# atmega328_Arduino.net
KiCad netlist of a schematic drawn in EAGLE
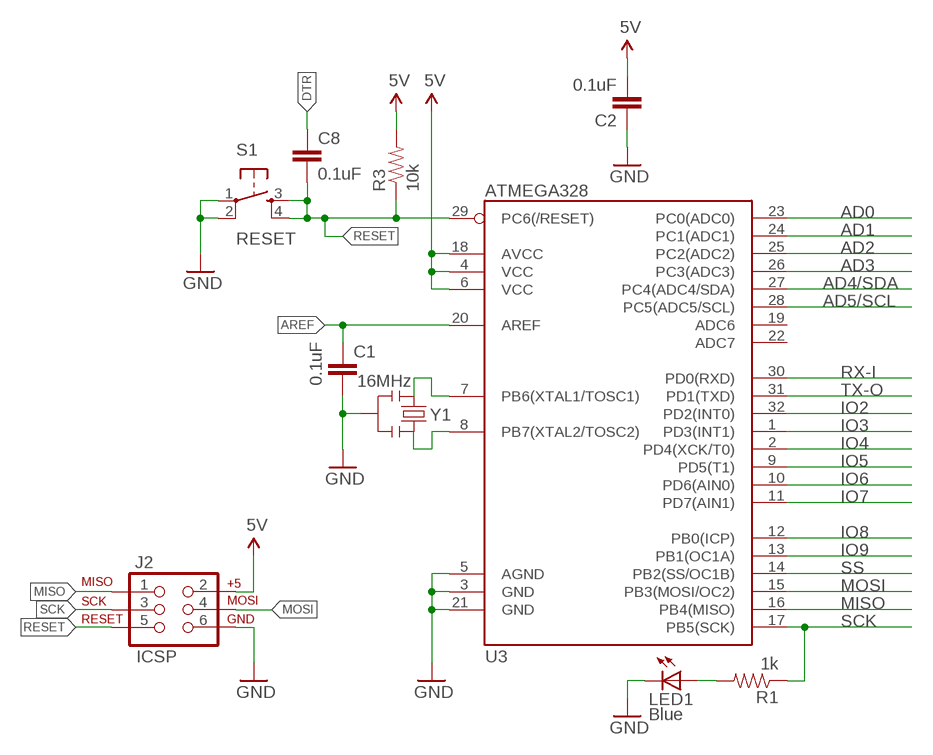
[diagram p0: schematic, sheet 1]

(export (version "E")
  (design (tool "Eeschema 10.0.6"))
  (components
    (comp (ref "C1")
      (value "0.1uF")
      (footprint "eagle-import:0603-CAP")
      (libsource (lib "eagle-import") (part "CAP0603-CAP"))
    )
    (comp (ref "C2")
      (value "0.1uF")
      (footprint "eagle-import:0603-CAP")
      (libsource (lib "eagle-import") (part "CAP0603-CAP"))
    )
    (comp (ref "C8")
      (value "0.1uF")
      (footprint "eagle-import:0603-CAP")
      (libsource (lib "eagle-import") (part "CAP0603-CAP"))
    )
    (comp (ref "J2")
      (value "ICSP")
      (footprint "eagle-import:2X3_SMT_POSTS")
      (libsource (lib "eagle-import") (part "AVR_SPI_PRG_6SMT_MALE"))
    )
    (comp (ref "LED1")
      (value "Blue")
      (footprint "eagle-import:LED-1206-NO_SILK")
      (libsource (lib "eagle-import") (part "LED1206-NS"))
    )
    (comp (ref "R1")
      (value "1k")
      (footprint "eagle-import:0603-RES")
      (libsource (lib "eagle-import") (part "RESISTOR0603-RES"))
    )
    (comp (ref "R3")
      (value "10k")
      (footprint "eagle-import:0603-RES")
      (libsource (lib "eagle-import") (part "RESISTOR0603-RES"))
    )
    (comp (ref "S1")
      (value "RESET")
      (footprint "eagle-import:TACTILE_SWITCH_SMD")
      (libsource (lib "eagle-import") (part "TAC_SWITCHSMD"))
    )
    (comp (ref "U3")
      (value "ATMEGA328")
      (footprint "eagle-import:TQFP32-08")
      (libsource (lib "eagle-import") (part "ATMEGA168"))
    )
    (comp (ref "Y1")
      (value "16MHz")
      (footprint "eagle-import:RESONATOR-SMD")
      (libsource (lib "eagle-import") (part "RESONATORSMD"))
    )
  )
  (nets
    (net (code "1") (name "/AD0") (class "Default")
      (node (ref "U3") (pin "23") (pinfunction "PC0(ADC0)_23") (pintype "bidirectional"))
    )
    (net (code "2") (name "/AD1") (class "Default")
      (node (ref "U3") (pin "24") (pinfunction "PC1(ADC1)_24") (pintype "bidirectional"))
    )
    (net (code "3") (name "/AD2") (class "Default")
      (node (ref "U3") (pin "25") (pinfunction "PC2(ADC2)_25") (pintype "bidirectional"))
    )
    (net (code "4") (name "/AD3") (class "Default")
      (node (ref "U3") (pin "26") (pinfunction "PC3(ADC3)_26") (pintype "bidirectional"))
    )
    (net (code "5") (name "/AD4{slash}SDA") (class "Default")
      (node (ref "U3") (pin "27") (pinfunction "PC4(ADC4/SDA)_27") (pintype "bidirectional"))
    )
    (net (code "6") (name "/AD5{slash}SCL") (class "Default")
      (node (ref "U3") (pin "28") (pinfunction "PC5(ADC5/SCL)_28") (pintype "bidirectional"))
    )
    (net (code "7") (name "/IO2") (class "Default")
      (node (ref "U3") (pin "32") (pinfunction "PD2(INT0)_32") (pintype "bidirectional"))
    )
    (net (code "8") (name "/IO3") (class "Default")
      (node (ref "U3") (pin "1") (pinfunction "PD3(INT1)_1") (pintype "bidirectional"))
    )
    (net (code "9") (name "/IO4") (class "Default")
      (node (ref "U3") (pin "2") (pinfunction "PD4(XCK/T0)_2") (pintype "bidirectional"))
    )
    (net (code "10") (name "/IO5") (class "Default")
      (node (ref "U3") (pin "9") (pinfunction "PD5(T1)_9") (pintype "bidirectional"))
    )
    (net (code "11") (name "/IO6") (class "Default")
      (node (ref "U3") (pin "10") (pinfunction "PD6(AIN0)_10") (pintype "bidirectional"))
    )
    (net (code "12") (name "/IO7") (class "Default")
      (node (ref "U3") (pin "11") (pinfunction "PD7(AIN1)_11") (pintype "bidirectional"))
    )
    (net (code "13") (name "/IO8") (class "Default")
      (node (ref "U3") (pin "12") (pinfunction "PB0(ICP)_12") (pintype "bidirectional"))
    )
    (net (code "14") (name "/IO9") (class "Default")
      (node (ref "U3") (pin "13") (pinfunction "PB1(OC1A)_13") (pintype "bidirectional"))
    )
    (net (code "15") (name "/RX-I") (class "Default")
      (node (ref "U3") (pin "30") (pinfunction "PD0(RXD)_30") (pintype "bidirectional"))
    )
    (net (code "16") (name "/SS") (class "Default")
      (node (ref "U3") (pin "14") (pinfunction "PB2(SS/OC1B)_14") (pintype "bidirectional"))
    )
    (net (code "17") (name "/TX-O") (class "Default")
      (node (ref "U3") (pin "31") (pinfunction "PD1(TXD)_31") (pintype "bidirectional"))
    )
    (net (code "18") (name "5V") (class "Default")
      (node (ref "C2") (pin "2") (pinfunction "2_2") (pintype "passive"))
      (node (ref "J2") (pin "2") (pinfunction "2_2") (pintype "passive"))
      (node (ref "R3") (pin "2") (pinfunction "2_2") (pintype "passive"))
      (node (ref "U3") (pin "18") (pinfunction "AVCC_18") (pintype "bidirectional"))
      (node (ref "U3") (pin "4") (pinfunction "VCC_4") (pintype "bidirectional"))
      (node (ref "U3") (pin "6") (pinfunction "VCC_6") (pintype "bidirectional"))
    )
    (net (code "19") (name "AREF") (class "Default")
      (node (ref "C1") (pin "1") (pinfunction "1_1") (pintype "passive"))
      (node (ref "U3") (pin "20") (pinfunction "AREF_20") (pintype "bidirectional"))
    )
    (net (code "20") (name "DTR") (class "Default")
      (node (ref "C8") (pin "1") (pinfunction "1_1") (pintype "passive"))
    )
    (net (code "21") (name "GND") (class "Default")
      (node (ref "C1") (pin "2") (pinfunction "2_2") (pintype "passive"))
      (node (ref "C2") (pin "1") (pinfunction "1_1") (pintype "passive"))
      (node (ref "J2") (pin "6") (pinfunction "6_6") (pintype "passive"))
      (node (ref "LED1") (pin "C") (pinfunction "C_C") (pintype "passive"))
      (node (ref "S1") (pin "1") (pinfunction "1_1") (pintype "passive"))
      (node (ref "S1") (pin "2") (pinfunction "2_2") (pintype "passive"))
      (node (ref "U3") (pin "21") (pinfunction "GND_21") (pintype "bidirectional"))
      (node (ref "U3") (pin "3") (pinfunction "GND_3") (pintype "bidirectional"))
      (node (ref "U3") (pin "5") (pinfunction "AGND_5") (pintype "bidirectional"))
      (node (ref "Y1") (pin "2") (pinfunction "2_2") (pintype "passive"))
    )
    (net (code "22") (name "MISO") (class "Default")
      (node (ref "J2") (pin "1") (pinfunction "1_1") (pintype "passive"))
      (node (ref "U3") (pin "16") (pinfunction "PB4(MISO)_16") (pintype "bidirectional"))
    )
    (net (code "23") (name "MOSI") (class "Default")
      (node (ref "J2") (pin "4") (pinfunction "4_4") (pintype "passive"))
      (node (ref "U3") (pin "15") (pinfunction "PB3(MOSI/OC2)_15") (pintype "bidirectional"))
    )
    (net (code "24") (name "Net-(LED1-PadA)") (class "Default")
      (node (ref "LED1") (pin "A") (pinfunction "A_A") (pintype "passive"))
      (node (ref "R1") (pin "2") (pinfunction "2_2") (pintype "passive"))
    )
    (net (code "25") (name "Net-(U3-PB6(XTAL1{slash}TOSC1))") (class "Default")
      (node (ref "U3") (pin "7") (pinfunction "PB6(XTAL1/TOSC1)_7") (pintype "bidirectional"))
      (node (ref "Y1") (pin "1") (pinfunction "1_1") (pintype "passive"))
    )
    (net (code "26") (name "Net-(U3-PB7(XTAL2{slash}TOSC2))") (class "Default")
      (node (ref "U3") (pin "8") (pinfunction "PB7(XTAL2/TOSC2)_8") (pintype "bidirectional"))
      (node (ref "Y1") (pin "3") (pinfunction "3_3") (pintype "passive"))
    )
    (net (code "27") (name "RESET") (class "Default")
      (node (ref "C8") (pin "2") (pinfunction "2_2") (pintype "passive"))
      (node (ref "J2") (pin "5") (pinfunction "5_5") (pintype "passive"))
      (node (ref "R3") (pin "1") (pinfunction "1_1") (pintype "passive"))
      (node (ref "S1") (pin "3") (pinfunction "3_3") (pintype "passive"))
      (node (ref "S1") (pin "4") (pinfunction "4_4") (pintype "passive"))
      (node (ref "U3") (pin "29") (pinfunction "PC6(/RESET)_29") (pintype "bidirectional"))
    )
    (net (code "28") (name "SCK") (class "Default")
      (node (ref "J2") (pin "3") (pinfunction "3_3") (pintype "passive"))
      (node (ref "R1") (pin "1") (pinfunction "1_1") (pintype "passive"))
      (node (ref "U3") (pin "17") (pinfunction "PB5(SCK)_17") (pintype "bidirectional"))
    )
    (net (code "29") (name "unconnected-(U3-ADC6-Pad19)") (class "Default")
      (node (ref "U3") (pin "19") (pinfunction "ADC6_19") (pintype "bidirectional"))
    )
    (net (code "30") (name "unconnected-(U3-ADC7-Pad22)") (class "Default")
      (node (ref "U3") (pin "22") (pinfunction "ADC7_22") (pintype "bidirectional"))
    )
  )
)
